# AirSensor.net
KiCad netlist of a schematic drawn in EAGLE
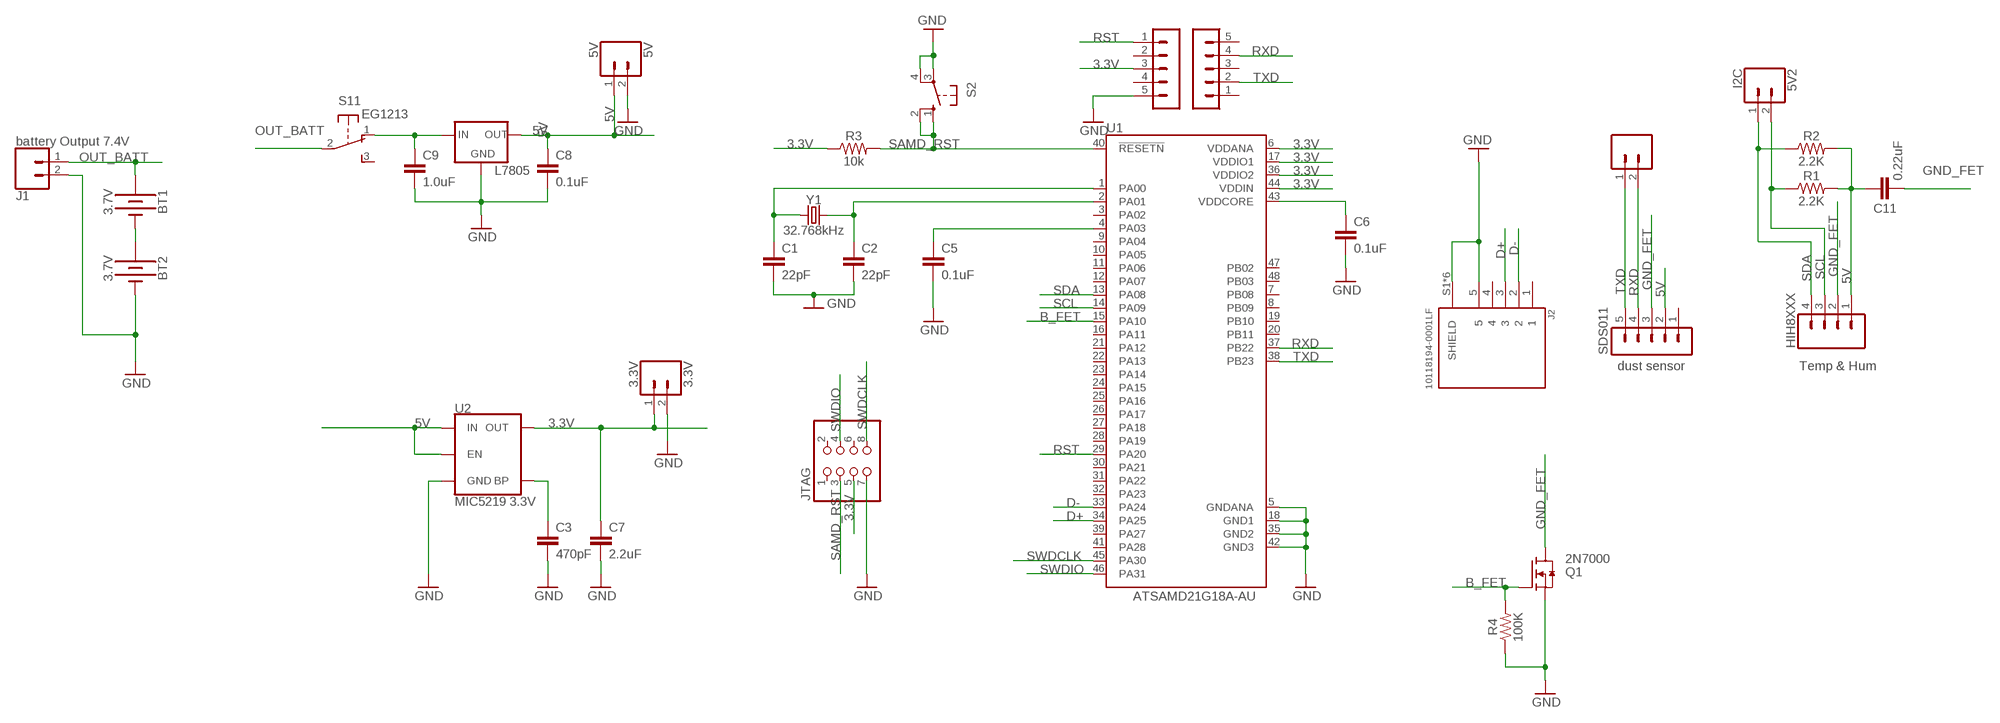
[diagram p0: schematic, sheet 1]

(export (version "E")
  (design (tool "Eeschema 10.0.6"))
  (components
    (comp (ref "3.3V")
      (value "3.3V")
      (footprint "eagle-import:1X02")
      (libsource (lib "eagle-import") (part "CONN_02"))
    )
    (comp (ref "5V")
      (value "5V")
      (footprint "eagle-import:1X02")
      (libsource (lib "eagle-import") (part "CONN_02"))
    )
    (comp (ref "5V1")
      (value "UART")
      (footprint "eagle-import:1X02")
      (libsource (lib "eagle-import") (part "CONN_02"))
    )
    (comp (ref "5V2")
      (value "I2C")
      (footprint "eagle-import:1X02")
      (libsource (lib "eagle-import") (part "CONN_02"))
    )
    (comp (ref "BT1")
      (value "3.7V")
      (footprint "eagle-import:BATTERY_18650-HOLDER")
      (libsource (lib "eagle-import") (part "BATTERY-18650"))
    )
    (comp (ref "BT2")
      (value "3.7V")
      (footprint "eagle-import:BATTERY_18650-HOLDER")
      (libsource (lib "eagle-import") (part "BATTERY-18650"))
    )
    (comp (ref "C1")
      (value "22pF")
      (footprint "eagle-import:0805")
      (libsource (lib "eagle-import") (part "1.0UF-0805-25V-10%"))
    )
    (comp (ref "C2")
      (value "22pF")
      (footprint "eagle-import:0805")
      (libsource (lib "eagle-import") (part "1.0UF-0805-25V-10%"))
    )
    (comp (ref "C3")
      (value "470pF")
      (footprint "eagle-import:0805")
      (libsource (lib "eagle-import") (part "1.0UF-0805-25V-10%"))
    )
    (comp (ref "C5")
      (value "0.1uF")
      (footprint "eagle-import:0805")
      (libsource (lib "eagle-import") (part "1.0UF-0805-25V-10%"))
    )
    (comp (ref "C6")
      (value "0.1uF")
      (footprint "eagle-import:0805")
      (libsource (lib "eagle-import") (part "1.0UF-0805-25V-10%"))
    )
    (comp (ref "C7")
      (value "2.2uF")
      (footprint "eagle-import:0805")
      (libsource (lib "eagle-import") (part "1.0UF-0805-25V-10%"))
    )
    (comp (ref "C8")
      (value "0.1uF")
      (footprint "eagle-import:0805")
      (libsource (lib "eagle-import") (part "1.0UF-0805-25V-10%"))
    )
    (comp (ref "C9")
      (value "1.0uF")
      (footprint "eagle-import:0805")
      (libsource (lib "eagle-import") (part "1.0UF-0805-25V-(+80/-20%)"))
    )
    (comp (ref "C11")
      (value "0.22uF")
      (footprint "eagle-import:0805")
      (libsource (lib "eagle-import") (part "1.0UF-0805-25V-10%"))
    )
    (comp (ref "HIH8XXX")
      (value "Temp & Hum")
      (footprint "eagle-import:1X04")
      (libsource (lib "eagle-import") (part "CONN_04"))
    )
    (comp (ref "J1")
      (value "battery Output 7.4V")
      (footprint "eagle-import:1X02")
      (libsource (lib "eagle-import") (part "CONN_02"))
    )
    (comp (ref "J2")
      (value "10118194-0001LF")
      (footprint "eagle-import:AMPHENOL_10118194-0001LF")
      (fields (field (name "MF") "Amphenol ICC (FCI)"))
      (libsource (lib "eagle-import") (part "10118194-0001LF"))
    )
    (comp (ref "JTAG")
      (value "PINHD-2X4")
      (footprint "eagle-import:2X04")
      (libsource (lib "eagle-import") (part "PINHD-2X4"))
    )
    (comp (ref "L7805")
      (value "V_REG_78XXSINK")
      (footprint "eagle-import:TO220-IGO")
      (libsource (lib "eagle-import") (part "V_REG_78XXSINK"))
    )
    (comp (ref "Q1")
      (value "2N7000")
      (footprint "eagle-import:TO92")
      (fields (field (name "MF") "STMicroelectronics"))
      (libsource (lib "eagle-import") (part "2N7000"))
    )
    (comp (ref "R1")
      (value "2.2K")
      (footprint "eagle-import:0805")
      (libsource (lib "eagle-import") (part "0.3OHM-0805-1/8W-1%"))
    )
    (comp (ref "R2")
      (value "2.2K")
      (footprint "eagle-import:0805")
      (libsource (lib "eagle-import") (part "0.3OHM-0805-1/8W-1%"))
    )
    (comp (ref "R3")
      (value "10k")
      (footprint "eagle-import:0805")
      (libsource (lib "eagle-import") (part "0.3OHM-0805-1/8W-1%"))
    )
    (comp (ref "R4")
      (value "100K")
      (footprint "eagle-import:0805")
      (libsource (lib "eagle-import") (part "0.3OHM-0805-1/8W-1%"))
    )
    (comp (ref "RN2483")
      (value "LoRa1")
      (footprint "eagle-import:MA05-1")
      (libsource (lib "eagle-import") (part "MA05-1"))
    )
    (comp (ref "RN2483_2")
      (value "LoRa_2")
      (footprint "eagle-import:MA05-1")
      (libsource (lib "eagle-import") (part "MA05-1"))
    )
    (comp (ref "S1")
      (value "EG1213")
      (footprint "eagle-import:EG1213")
      (fields (field (name "MF") "E-Switch"))
      (libsource (lib "eagle-import") (part "EG1213"))
    )
    (comp (ref "S2")
      (value "10-XX")
      (footprint "eagle-import:B3F-10XX")
      (fields (field (name "MPN") "B3F-1000"))
      (libsource (lib "eagle-import") (part "10-XX"))
    )
    (comp (ref "SDS011")
      (value "dust sensor")
      (footprint "eagle-import:MA05-1")
      (libsource (lib "eagle-import") (part "MA05-1"))
    )
    (comp (ref "U1")
      (value "ATSAMD21G18A-AU")
      (footprint "eagle-import:QFP50P900X900X120-48N")
      (fields (field (name "MF") "Microchip"))
      (libsource (lib "eagle-import") (part "ATSAMD21G18A-AU"))
    )
    (comp (ref "U2")
      (value "MIC5219 3.3V")
      (footprint "eagle-import:SOT23-5")
      (libsource (lib "eagle-import") (part "V_REG_MIC52193.3V"))
    )
    (comp (ref "Y1")
      (value "32.768kHz")
      (footprint "eagle-import:CRYSTAL-SMD-3.2X1.5MM")
      (libsource (lib "eagle-import") (part "CRYSTAL-32.768KHZSMD-3.2X1.5"))
    )
  )
  (nets
    (net (code "1") (name "/3.3V") (class "Default")
      (node (ref "3.3V") (pin "1") (pinfunction "1_1") (pintype "passive"))
      (node (ref "C7") (pin "1") (pinfunction "1_1") (pintype "passive"))
      (node (ref "JTAG") (pin "5") (pinfunction "5_5") (pintype "passive"))
      (node (ref "R3") (pin "1") (pinfunction "1_1") (pintype "passive"))
      (node (ref "RN2483") (pin "3") (pinfunction "3_3") (pintype "passive"))
      (node (ref "U1") (pin "17") (pinfunction "VDDIO1_17") (pintype "power_in"))
      (node (ref "U1") (pin "36") (pinfunction "VDDIO2_36") (pintype "power_in"))
      (node (ref "U1") (pin "44") (pinfunction "VDDIN_44") (pintype "power_in"))
      (node (ref "U1") (pin "6") (pinfunction "VDDANA_6") (pintype "power_in"))
      (node (ref "U2") (pin "5") (pinfunction "OUT_5") (pintype "passive"))
    )
    (net (code "2") (name "/5V") (class "Default")
      (node (ref "5V") (pin "1") (pinfunction "1_1") (pintype "passive"))
      (node (ref "C11") (pin "1") (pinfunction "1_1") (pintype "passive"))
      (node (ref "C8") (pin "1") (pinfunction "1_1") (pintype "passive"))
      (node (ref "HIH8XXX") (pin "1") (pinfunction "1_1") (pintype "passive"))
      (node (ref "L7805") (pin "OUT") (pinfunction "OUT_OUT") (pintype "passive"))
      (node (ref "R1") (pin "2") (pinfunction "2_2") (pintype "passive"))
      (node (ref "R2") (pin "2") (pinfunction "2_2") (pintype "passive"))
      (node (ref "SDS011") (pin "2") (pinfunction "2_2") (pintype "passive"))
      (node (ref "U2") (pin "1") (pinfunction "IN_1") (pintype "input"))
      (node (ref "U2") (pin "3") (pinfunction "EN_3") (pintype "input"))
    )
    (net (code "3") (name "/B_FET") (class "Default")
      (node (ref "Q1") (pin "2") (pinfunction "G_2") (pintype "passive"))
      (node (ref "R4") (pin "2") (pinfunction "2_2") (pintype "passive"))
      (node (ref "U1") (pin "15") (pinfunction "PA10_15") (pintype "bidirectional"))
    )
    (net (code "4") (name "/D+") (class "Default")
      (node (ref "J2") (pin "3") (pinfunction "3_3") (pintype "passive"))
      (node (ref "U1") (pin "34") (pinfunction "PA25_34") (pintype "bidirectional"))
    )
    (net (code "5") (name "/D-") (class "Default")
      (node (ref "J2") (pin "2") (pinfunction "2_2") (pintype "passive"))
      (node (ref "U1") (pin "33") (pinfunction "PA24_33") (pintype "bidirectional"))
    )
    (net (code "6") (name "/GND_FET") (class "Default")
      (node (ref "C11") (pin "2") (pinfunction "2_2") (pintype "passive"))
      (node (ref "HIH8XXX") (pin "2") (pinfunction "2_2") (pintype "passive"))
      (node (ref "Q1") (pin "3") (pinfunction "D_3") (pintype "passive"))
      (node (ref "SDS011") (pin "3") (pinfunction "3_3") (pintype "passive"))
    )
    (net (code "7") (name "/OUT_BATT") (class "Default")
      (node (ref "BT1") (pin "PWR@1") (pinfunction "+_PWR@1") (pintype "power_in"))
      (node (ref "C9") (pin "1") (pinfunction "1_1") (pintype "passive"))
      (node (ref "J1") (pin "1") (pinfunction "1_1") (pintype "passive"))
      (node (ref "L7805") (pin "IN") (pinfunction "IN_IN") (pintype "input"))
      (node (ref "S1") (pin "1") (pinfunction "O_1") (pintype "passive"))
      (node (ref "S1") (pin "2") (pinfunction "P_2") (pintype "passive"))
    )
    (net (code "8") (name "/RST") (class "Default")
      (node (ref "RN2483") (pin "1") (pinfunction "1_1") (pintype "passive"))
      (node (ref "U1") (pin "29") (pinfunction "PA20_29") (pintype "bidirectional"))
    )
    (net (code "9") (name "/RXD") (class "Default")
      (node (ref "5V1") (pin "2") (pinfunction "2_2") (pintype "passive"))
      (node (ref "RN2483_2") (pin "4") (pinfunction "4_4") (pintype "passive"))
      (node (ref "SDS011") (pin "4") (pinfunction "4_4") (pintype "passive"))
      (node (ref "U1") (pin "37") (pinfunction "PB22_37") (pintype "bidirectional"))
    )
    (net (code "10") (name "/SAMD_RST") (class "Default")
      (node (ref "JTAG") (pin "3") (pinfunction "3_3") (pintype "passive"))
      (node (ref "R3") (pin "2") (pinfunction "2_2") (pintype "passive"))
      (node (ref "S2") (pin "1") (pinfunction "S_1") (pintype "passive"))
      (node (ref "S2") (pin "2") (pinfunction "S1_2") (pintype "passive"))
      (node (ref "U1") (pin "40") (pinfunction "~{RESETN}_40") (pintype "input"))
    )
    (net (code "11") (name "/SCL") (class "Default")
      (node (ref "5V2") (pin "2") (pinfunction "2_2") (pintype "passive"))
      (node (ref "HIH8XXX") (pin "3") (pinfunction "3_3") (pintype "passive"))
      (node (ref "R1") (pin "1") (pinfunction "1_1") (pintype "passive"))
      (node (ref "U1") (pin "14") (pinfunction "PA09_14") (pintype "bidirectional"))
    )
    (net (code "12") (name "/SDA") (class "Default")
      (node (ref "5V2") (pin "1") (pinfunction "1_1") (pintype "passive"))
      (node (ref "HIH8XXX") (pin "4") (pinfunction "4_4") (pintype "passive"))
      (node (ref "R2") (pin "1") (pinfunction "1_1") (pintype "passive"))
      (node (ref "U1") (pin "13") (pinfunction "PA08_13") (pintype "bidirectional"))
    )
    (net (code "13") (name "/SWDCLK") (class "Default")
      (node (ref "JTAG") (pin "8") (pinfunction "8_8") (pintype "passive"))
      (node (ref "U1") (pin "45") (pinfunction "PA30_45") (pintype "bidirectional"))
    )
    (net (code "14") (name "/SWDIO") (class "Default")
      (node (ref "JTAG") (pin "4") (pinfunction "4_4") (pintype "passive"))
      (node (ref "U1") (pin "46") (pinfunction "PA31_46") (pintype "bidirectional"))
    )
    (net (code "15") (name "/TXD") (class "Default")
      (node (ref "5V1") (pin "1") (pinfunction "1_1") (pintype "passive"))
      (node (ref "RN2483_2") (pin "2") (pinfunction "2_2") (pintype "passive"))
      (node (ref "SDS011") (pin "5") (pinfunction "5_5") (pintype "passive"))
      (node (ref "U1") (pin "38") (pinfunction "PB23_38") (pintype "bidirectional"))
    )
    (net (code "16") (name "GND") (class "Default")
      (node (ref "3.3V") (pin "2") (pinfunction "2_2") (pintype "passive"))
      (node (ref "5V") (pin "2") (pinfunction "2_2") (pintype "passive"))
      (node (ref "BT2") (pin "GND@1") (pinfunction "-_GND@1") (pintype "power_in"))
      (node (ref "C1") (pin "2") (pinfunction "2_2") (pintype "passive"))
      (node (ref "C2") (pin "2") (pinfunction "2_2") (pintype "passive"))
      (node (ref "C3") (pin "2") (pinfunction "2_2") (pintype "passive"))
      (node (ref "C5") (pin "2") (pinfunction "2_2") (pintype "passive"))
      (node (ref "C6") (pin "2") (pinfunction "2_2") (pintype "passive"))
      (node (ref "C7") (pin "2") (pinfunction "2_2") (pintype "passive"))
      (node (ref "C8") (pin "2") (pinfunction "2_2") (pintype "passive"))
      (node (ref "C9") (pin "2") (pinfunction "2_2") (pintype "passive"))
      (node (ref "J1") (pin "2") (pinfunction "2_2") (pintype "passive"))
      (node (ref "J2") (pin "5") (pinfunction "5_5") (pintype "passive"))
      (node (ref "J2") (pin "S1") (pinfunction "SHIELD_S1") (pintype "passive"))
      (node (ref "J2") (pin "S2") (pinfunction "SHIELD_S2") (pintype "passive"))
      (node (ref "J2") (pin "S3") (pinfunction "SHIELD_S3") (pintype "passive"))
      (node (ref "J2") (pin "S4") (pinfunction "SHIELD_S4") (pintype "passive"))
      (node (ref "J2") (pin "S5") (pinfunction "SHIELD_S5") (pintype "passive"))
      (node (ref "J2") (pin "S6") (pinfunction "SHIELD_S6") (pintype "passive"))
      (node (ref "JTAG") (pin "7") (pinfunction "7_7") (pintype "passive"))
      (node (ref "L7805") (pin "GND") (pinfunction "GND_GND") (pintype "input"))
      (node (ref "Q1") (pin "1") (pinfunction "S_1") (pintype "passive"))
      (node (ref "R4") (pin "1") (pinfunction "1_1") (pintype "passive"))
      (node (ref "RN2483") (pin "5") (pinfunction "5_5") (pintype "passive"))
      (node (ref "S2") (pin "3") (pinfunction "P_3") (pintype "passive"))
      (node (ref "S2") (pin "4") (pinfunction "P1_4") (pintype "passive"))
      (node (ref "U1") (pin "18") (pinfunction "GND1_18") (pintype "power_in"))
      (node (ref "U1") (pin "35") (pinfunction "GND2_35") (pintype "power_in"))
      (node (ref "U1") (pin "42") (pinfunction "GND3_42") (pintype "power_in"))
      (node (ref "U1") (pin "5") (pinfunction "GNDANA_5") (pintype "power_in"))
      (node (ref "U2") (pin "2") (pinfunction "GND_2") (pintype "input"))
    )
    (net (code "17") (name "Net-(BT1--)") (class "Default")
      (node (ref "BT1") (pin "GND@1") (pinfunction "-_GND@1") (pintype "power_in"))
      (node (ref "BT2") (pin "PWR@1") (pinfunction "+_PWR@1") (pintype "power_in"))
    )
    (net (code "18") (name "Net-(U1-PA00)") (class "Default")
      (node (ref "C1") (pin "1") (pinfunction "1_1") (pintype "passive"))
      (node (ref "U1") (pin "1") (pinfunction "PA00_1") (pintype "bidirectional"))
      (node (ref "Y1") (pin "P$1") (pinfunction "1_P$1") (pintype "passive"))
    )
    (net (code "19") (name "Net-(U1-PA01)") (class "Default")
      (node (ref "C2") (pin "1") (pinfunction "1_1") (pintype "passive"))
      (node (ref "U1") (pin "2") (pinfunction "PA01_2") (pintype "bidirectional"))
      (node (ref "Y1") (pin "P$2") (pinfunction "2_P$2") (pintype "passive"))
    )
    (net (code "20") (name "Net-(U1-PA03)") (class "Default")
      (node (ref "C5") (pin "1") (pinfunction "1_1") (pintype "passive"))
      (node (ref "U1") (pin "4") (pinfunction "PA03_4") (pintype "bidirectional"))
    )
    (net (code "21") (name "Net-(U1-VDDCORE)") (class "Default")
      (node (ref "C6") (pin "1") (pinfunction "1_1") (pintype "passive"))
      (node (ref "U1") (pin "43") (pinfunction "VDDCORE_43") (pintype "power_in"))
    )
    (net (code "22") (name "Net-(U2-BP)") (class "Default")
      (node (ref "C3") (pin "1") (pinfunction "1_1") (pintype "passive"))
      (node (ref "U2") (pin "4") (pinfunction "BP_4") (pintype "input"))
    )
    (net (code "23") (name "unconnected-(J2-Pad1)") (class "Default")
      (node (ref "J2") (pin "1") (pinfunction "1_1") (pintype "passive"))
    )
    (net (code "24") (name "unconnected-(J2-Pad4)") (class "Default")
      (node (ref "J2") (pin "4") (pinfunction "4_4") (pintype "passive"))
    )
    (net (code "25") (name "unconnected-(JTAG-Pad1)") (class "Default")
      (node (ref "JTAG") (pin "1") (pinfunction "1_1") (pintype "passive"))
    )
    (net (code "26") (name "unconnected-(JTAG-Pad2)") (class "Default")
      (node (ref "JTAG") (pin "2") (pinfunction "2_2") (pintype "passive"))
    )
    (net (code "27") (name "unconnected-(JTAG-Pad6)") (class "Default")
      (node (ref "JTAG") (pin "6") (pinfunction "6_6") (pintype "passive"))
    )
    (net (code "28") (name "unconnected-(RN2483-Pad2)") (class "Default")
      (node (ref "RN2483") (pin "2") (pinfunction "2_2") (pintype "passive"))
    )
    (net (code "29") (name "unconnected-(RN2483-Pad4)") (class "Default")
      (node (ref "RN2483") (pin "4") (pinfunction "4_4") (pintype "passive"))
    )
    (net (code "30") (name "unconnected-(RN2483_2-Pad1)") (class "Default")
      (node (ref "RN2483_2") (pin "1") (pinfunction "1_1") (pintype "passive"))
    )
    (net (code "31") (name "unconnected-(RN2483_2-Pad3)") (class "Default")
      (node (ref "RN2483_2") (pin "3") (pinfunction "3_3") (pintype "passive"))
    )
    (net (code "32") (name "unconnected-(RN2483_2-Pad5)") (class "Default")
      (node (ref "RN2483_2") (pin "5") (pinfunction "5_5") (pintype "passive"))
    )
    (net (code "33") (name "unconnected-(S1A-S-Pad3)") (class "Default")
      (node (ref "S1") (pin "3") (pinfunction "S_3") (pintype "passive"))
    )
    (net (code "34") (name "unconnected-(SDS011-Pad1)") (class "Default")
      (node (ref "SDS011") (pin "1") (pinfunction "1_1") (pintype "passive"))
    )
    (net (code "35") (name "unconnected-(U1-PA02-Pad3)") (class "Default")
      (node (ref "U1") (pin "3") (pinfunction "PA02_3") (pintype "bidirectional"))
    )
    (net (code "36") (name "unconnected-(U1-PA04-Pad9)") (class "Default")
      (node (ref "U1") (pin "9") (pinfunction "PA04_9") (pintype "bidirectional"))
    )
    (net (code "37") (name "unconnected-(U1-PA05-Pad10)") (class "Default")
      (node (ref "U1") (pin "10") (pinfunction "PA05_10") (pintype "bidirectional"))
    )
    (net (code "38") (name "unconnected-(U1-PA06-Pad11)") (class "Default")
      (node (ref "U1") (pin "11") (pinfunction "PA06_11") (pintype "bidirectional"))
    )
    (net (code "39") (name "unconnected-(U1-PA07-Pad12)") (class "Default")
      (node (ref "U1") (pin "12") (pinfunction "PA07_12") (pintype "bidirectional"))
    )
    (net (code "40") (name "unconnected-(U1-PA11-Pad16)") (class "Default")
      (node (ref "U1") (pin "16") (pinfunction "PA11_16") (pintype "bidirectional"))
    )
    (net (code "41") (name "unconnected-(U1-PA12-Pad21)") (class "Default")
      (node (ref "U1") (pin "21") (pinfunction "PA12_21") (pintype "bidirectional"))
    )
    (net (code "42") (name "unconnected-(U1-PA13-Pad22)") (class "Default")
      (node (ref "U1") (pin "22") (pinfunction "PA13_22") (pintype "bidirectional"))
    )
    (net (code "43") (name "unconnected-(U1-PA14-Pad23)") (class "Default")
      (node (ref "U1") (pin "23") (pinfunction "PA14_23") (pintype "bidirectional"))
    )
    (net (code "44") (name "unconnected-(U1-PA15-Pad24)") (class "Default")
      (node (ref "U1") (pin "24") (pinfunction "PA15_24") (pintype "bidirectional"))
    )
    (net (code "45") (name "unconnected-(U1-PA16-Pad25)") (class "Default")
      (node (ref "U1") (pin "25") (pinfunction "PA16_25") (pintype "bidirectional"))
    )
    (net (code "46") (name "unconnected-(U1-PA17-Pad26)") (class "Default")
      (node (ref "U1") (pin "26") (pinfunction "PA17_26") (pintype "bidirectional"))
    )
    (net (code "47") (name "unconnected-(U1-PA18-Pad27)") (class "Default")
      (node (ref "U1") (pin "27") (pinfunction "PA18_27") (pintype "bidirectional"))
    )
    (net (code "48") (name "unconnected-(U1-PA19-Pad28)") (class "Default")
      (node (ref "U1") (pin "28") (pinfunction "PA19_28") (pintype "bidirectional"))
    )
    (net (code "49") (name "unconnected-(U1-PA21-Pad30)") (class "Default")
      (node (ref "U1") (pin "30") (pinfunction "PA21_30") (pintype "bidirectional"))
    )
    (net (code "50") (name "unconnected-(U1-PA22-Pad31)") (class "Default")
      (node (ref "U1") (pin "31") (pinfunction "PA22_31") (pintype "bidirectional"))
    )
    (net (code "51") (name "unconnected-(U1-PA23-Pad32)") (class "Default")
      (node (ref "U1") (pin "32") (pinfunction "PA23_32") (pintype "bidirectional"))
    )
    (net (code "52") (name "unconnected-(U1-PA27-Pad39)") (class "Default")
      (node (ref "U1") (pin "39") (pinfunction "PA27_39") (pintype "bidirectional"))
    )
    (net (code "53") (name "unconnected-(U1-PA28-Pad41)") (class "Default")
      (node (ref "U1") (pin "41") (pinfunction "PA28_41") (pintype "bidirectional"))
    )
    (net (code "54") (name "unconnected-(U1-PB02-Pad47)") (class "Default")
      (node (ref "U1") (pin "47") (pinfunction "PB02_47") (pintype "bidirectional"))
    )
    (net (code "55") (name "unconnected-(U1-PB03-Pad48)") (class "Default")
      (node (ref "U1") (pin "48") (pinfunction "PB03_48") (pintype "bidirectional"))
    )
    (net (code "56") (name "unconnected-(U1-PB08-Pad7)") (class "Default")
      (node (ref "U1") (pin "7") (pinfunction "PB08_7") (pintype "bidirectional"))
    )
    (net (code "57") (name "unconnected-(U1-PB09-Pad8)") (class "Default")
      (node (ref "U1") (pin "8") (pinfunction "PB09_8") (pintype "bidirectional"))
    )
    (net (code "58") (name "unconnected-(U1-PB10-Pad19)") (class "Default")
      (node (ref "U1") (pin "19") (pinfunction "PB10_19") (pintype "bidirectional"))
    )
    (net (code "59") (name "unconnected-(U1-PB11-Pad20)") (class "Default")
      (node (ref "U1") (pin "20") (pinfunction "PB11_20") (pintype "bidirectional"))
    )
  )
)
